# main_2023-11-12.net
KiCad netlist of a schematic drawn in Altium Designer
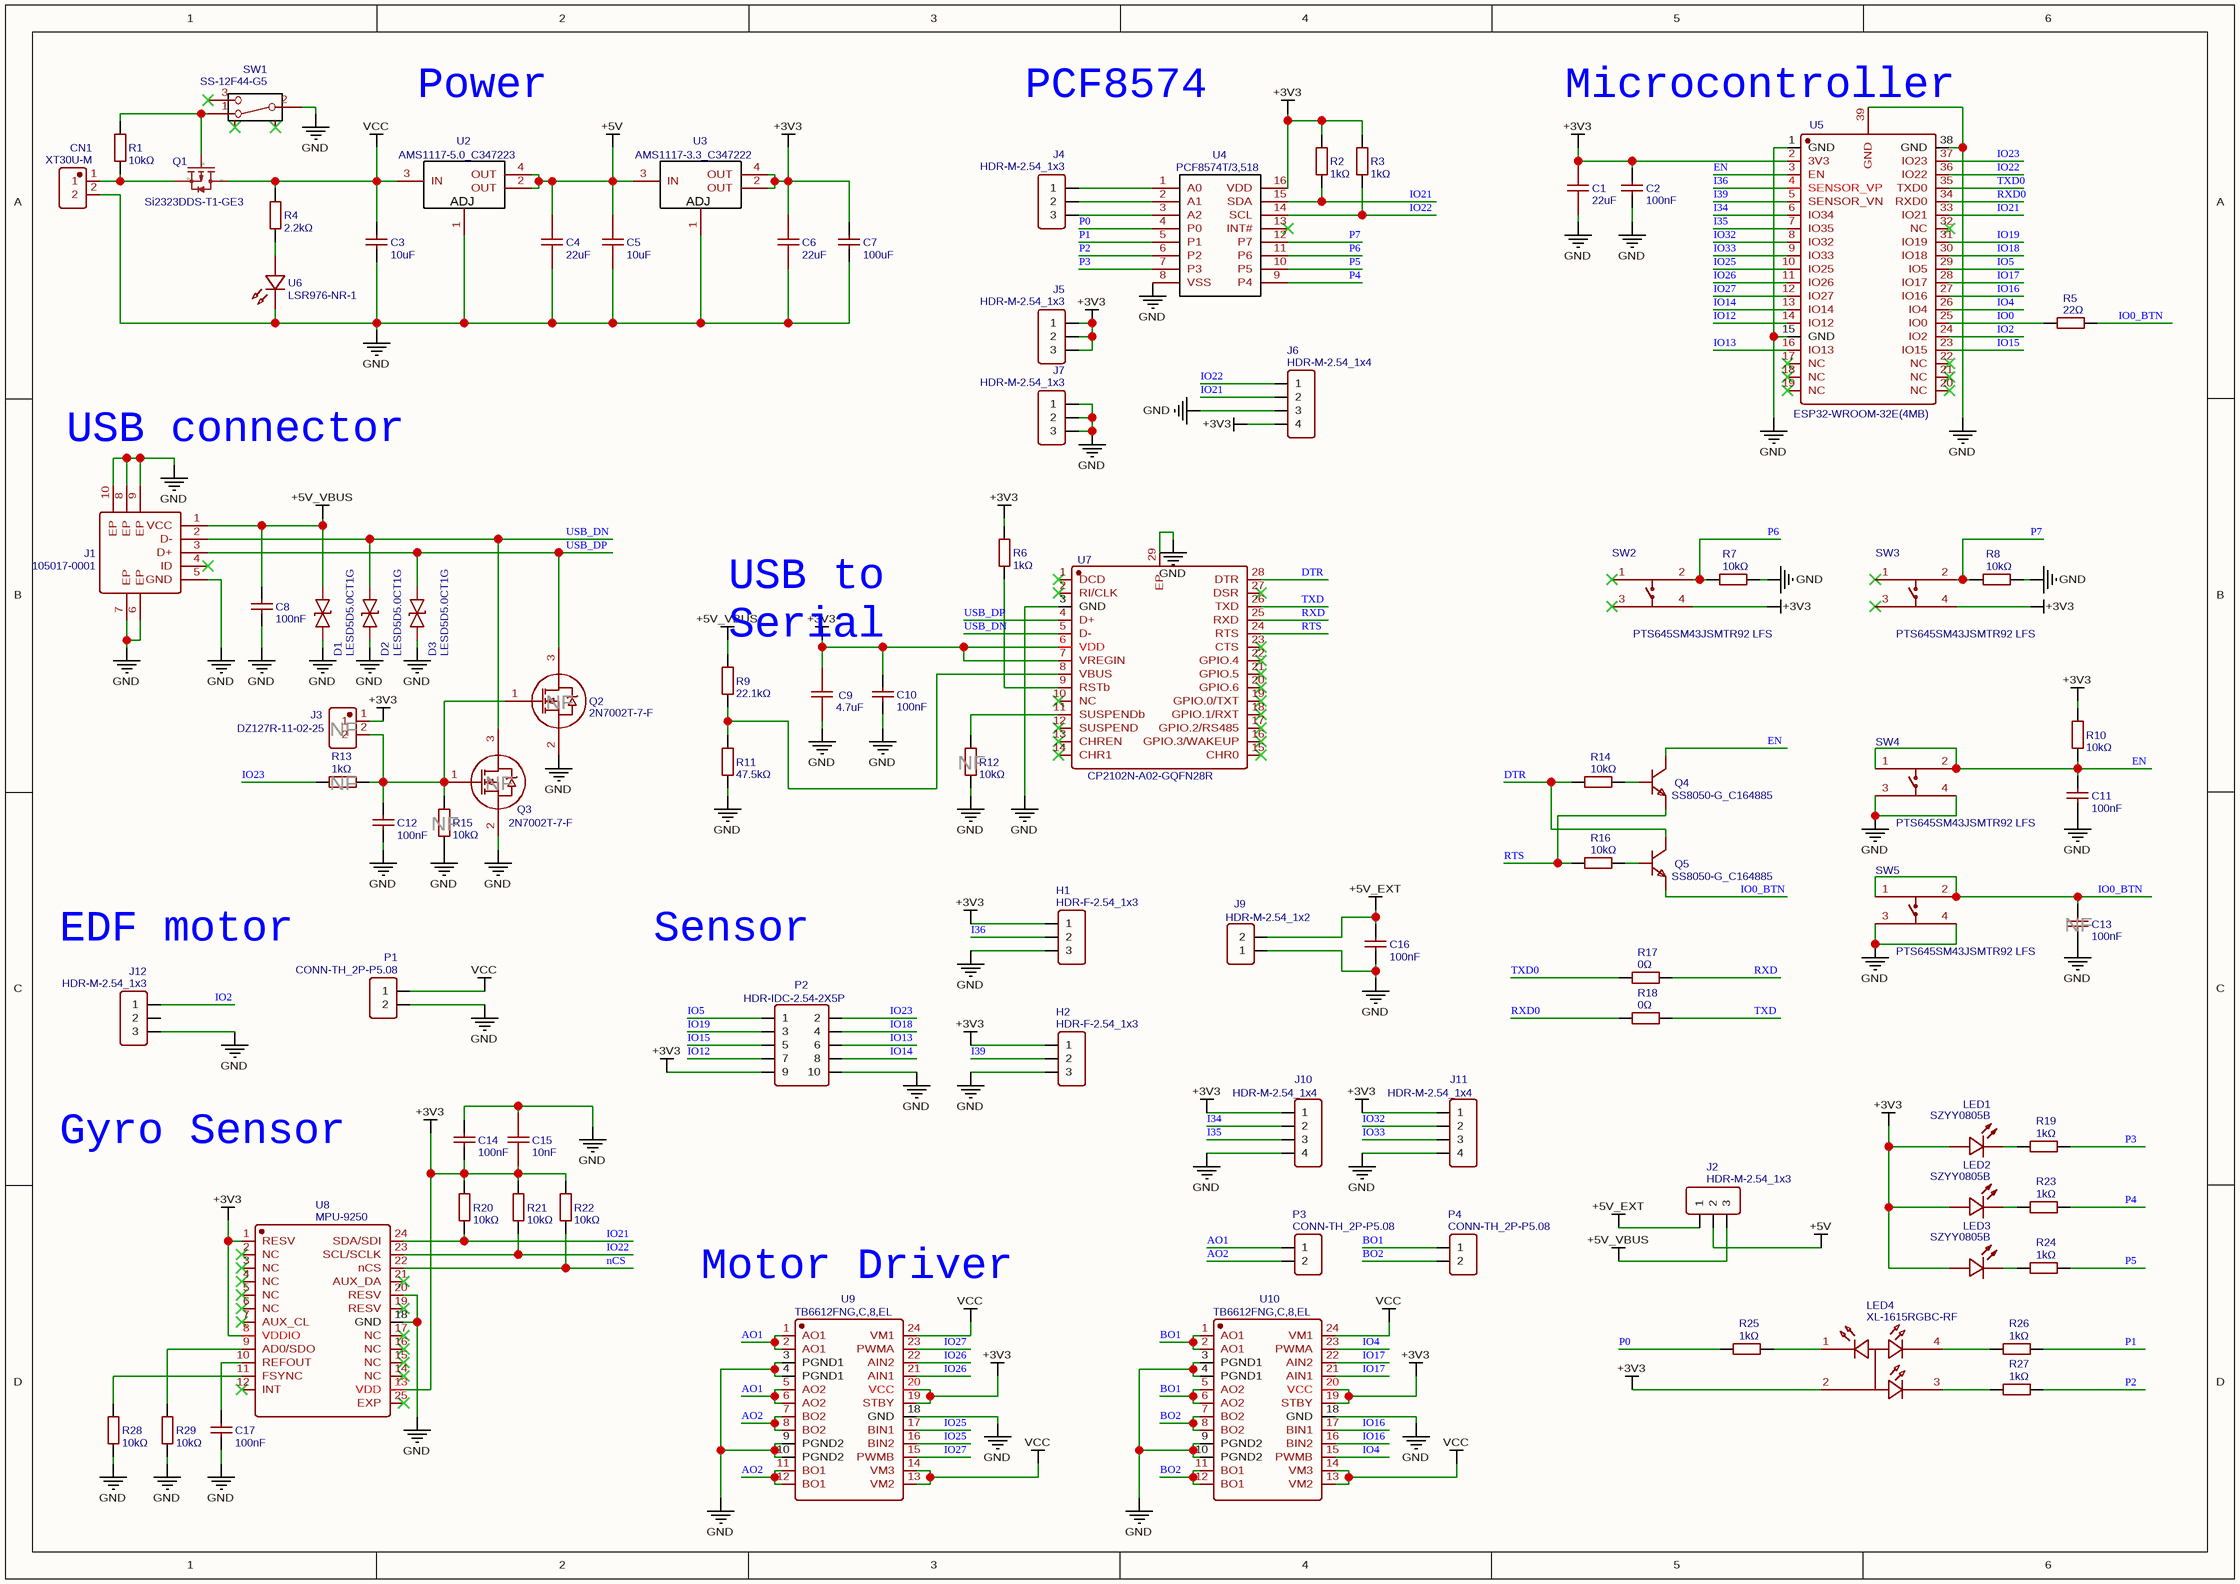
[diagram p0: main_2023-11-12.schdoc]

(export (version "E")
  (design (tool "Eeschema 10.0.6"))
  (components
    (comp (ref "C1")
      (value "22uF")
      (fields
        (field (name "MANUFACTURER") "SAMSUNG(三星)")
        (field (name "MANUFACTURER PART") "CL21A226MAYNNNE")
        (field (name "CONTRIBUTOR") "LCSC")
      )
      (libsource (lib "altium-import") (part "root_3_22uF_"))
    )
    (comp (ref "C2")
      (value "100nF")
      (fields
        (field (name "MANUFACTURER PART") "CL05B104KO5NNNC")
        (field (name "MANUFACTURER") "SAMSUNG(三星)")
      )
      (libsource (lib "altium-import") (part "root_3_100nF_"))
    )
    (comp (ref "C3")
      (value "10uF")
      (fields
        (field (name "MANUFACTURER PART") "CL21A106KOQNNNE")
        (field (name "MANUFACTURER") "SAMSUNG(三星)")
      )
      (libsource (lib "altium-import") (part "root_3_10uF_"))
    )
    (comp (ref "C4")
      (value "22uF")
      (fields
        (field (name "MANUFACTURER") "SAMSUNG(三星)")
        (field (name "MANUFACTURER PART") "CL21A226MAQNNNE")
      )
      (libsource (lib "altium-import") (part "root_3_22uF_"))
    )
    (comp (ref "C5")
      (value "10uF")
      (fields
        (field (name "MANUFACTURER") "SAMSUNG(三星)")
        (field (name "MANUFACTURER PART") "CL05A106MP5NUNC")
        (field (name "CONTRIBUTOR") "LCSC")
      )
      (libsource (lib "") (part "root_3_10uF__1"))
    )
    (comp (ref "C6")
      (value "22uF")
      (fields
        (field (name "MANUFACTURER") "SAMSUNG(三星)")
        (field (name "MANUFACTURER PART") "CL21A226MAQNNNE")
      )
      (libsource (lib "altium-import") (part "root_3_22uF_"))
    )
    (comp (ref "C7")
      (value "100uF")
      (fields
        (field (name "MANUFACTURER PART") "CL31A107MQHNNNE")
        (field (name "MANUFACTURER") "SAMSUNG(三星)")
      )
      (libsource (lib "altium-import") (part "root_3_100uF_"))
    )
    (comp (ref "C8")
      (value "100nF")
      (fields
        (field (name "MANUFACTURER PART") "CL05B104KO5NNNC")
        (field (name "MANUFACTURER") "SAMSUNG(三星)")
      )
      (libsource (lib "altium-import") (part "root_3_100nF_"))
    )
    (comp (ref "C9")
      (value "4.7uF")
      (fields
        (field (name "MANUFACTURER") "SAMSUNG(三星)")
        (field (name "MANUFACTURER PART") "CL05A475KP5NRNC")
        (field (name "CONTRIBUTOR") "LCSC")
      )
      (libsource (lib "altium-import") (part "root_0_4.7uF_"))
    )
    (comp (ref "C10")
      (value "100nF")
      (fields
        (field (name "MANUFACTURER PART") "CL05B104KO5NNNC")
        (field (name "MANUFACTURER") "SAMSUNG(三星)")
      )
      (libsource (lib "altium-import") (part "root_3_100nF_"))
    )
    (comp (ref "C11")
      (value "100nF")
      (fields
        (field (name "MANUFACTURER PART") "CL05B104KO5NNNC")
        (field (name "MANUFACTURER") "SAMSUNG(三星)")
      )
      (libsource (lib "altium-import") (part "root_3_100nF_"))
    )
    (comp (ref "C12")
      (value "100nF")
      (fields
        (field (name "MANUFACTURER PART") "CL05B104KO5NNNC")
        (field (name "MANUFACTURER") "SAMSUNG(三星)")
      )
      (libsource (lib "altium-import") (part "root_3_100nF_"))
    )
    (comp (ref "C13")
      (value "100nF")
      (fields
        (field (name "MANUFACTURER PART") "CL05B104KO5NNNC")
        (field (name "MANUFACTURER") "SAMSUNG(三星)")
      )
      (libsource (lib "altium-import") (part "root_3_100nF_"))
    )
    (comp (ref "C14")
      (value "100nF")
      (fields
        (field (name "MANUFACTURER PART") "CL05B104KO5NNNC")
        (field (name "MANUFACTURER") "SAMSUNG(三星)")
      )
      (libsource (lib "altium-import") (part "root_1_100nF_"))
    )
    (comp (ref "C15")
      (value "10nF")
      (fields
        (field (name "MANUFACTURER") "SAMSUNG(三星)")
        (field (name "MANUFACTURER PART") "CL05B103JO5NNNC")
        (field (name "CONTRIBUTOR") "LCSC")
      )
      (libsource (lib "altium-import") (part "root_0_10nF_"))
    )
    (comp (ref "C16")
      (value "100nF")
      (fields
        (field (name "MANUFACTURER PART") "CL05B104KO5NNNC")
        (field (name "MANUFACTURER") "SAMSUNG(三星)")
      )
      (libsource (lib "altium-import") (part "root_1_100nF_"))
    )
    (comp (ref "C17")
      (value "100nF")
      (fields
        (field (name "MANUFACTURER PART") "CL05B104KO5NNNC")
        (field (name "MANUFACTURER") "SAMSUNG(三星)")
      )
      (libsource (lib "altium-import") (part "root_3_100nF_"))
    )
    (comp (ref "CN1")
      (value "XT30U-M")
      (fields (field (name "MANUFACTURER") "AMASS(艾迈斯)") (field (name "CONTRIBUTOR") "lcsc"))
      (libsource (lib "altium-import") (part "root_0_XT30U-M_"))
    )
    (comp (ref "D1")
      (value "LESD5D5.0CT1G")
      (fields (field (name "MANUFACTURER") "LRC(乐山无线电)") (field (name "CONTRIBUTOR") "LCSC"))
      (libsource (lib "altium-import") (part "root_3_LESD5D5.0CT1G_"))
    )
    (comp (ref "D2")
      (value "LESD5D5.0CT1G")
      (fields (field (name "MANUFACTURER") "LRC(乐山无线电)") (field (name "CONTRIBUTOR") "LCSC"))
      (libsource (lib "altium-import") (part "root_3_LESD5D5.0CT1G_"))
    )
    (comp (ref "D3")
      (value "LESD5D5.0CT1G")
      (fields (field (name "MANUFACTURER") "LRC(乐山无线电)") (field (name "CONTRIBUTOR") "LCSC"))
      (libsource (lib "altium-import") (part "root_3_LESD5D5.0CT1G_"))
    )
    (comp (ref "H1")
      (value "HDR-F-2.54_1x3")
      (fields (field (name "CONTRIBUTOR") "LCEDA_Lib"))
      (libsource (lib "altium-import") (part "root_0_HDR-F-2.54_1x3_"))
    )
    (comp (ref "H2")
      (value "HDR-F-2.54_1x3")
      (fields (field (name "CONTRIBUTOR") "LCEDA_Lib"))
      (libsource (lib "altium-import") (part "root_0_HDR-F-2.54_1x3_"))
    )
    (comp (ref "J1")
      (value "105017-0001")
      (fields
        (field (name "MANUFACTURER") "MOLEX")
        (field (name "MANUFACTURER PART") "1050170001")
        (field (name "CONTRIBUTOR") "LCSC")
      )
      (libsource (lib "altium-import") (part "root_0_105017-0001_"))
    )
    (comp (ref "J2")
      (value "HDR-M-2.54_1x3")
      (fields (field (name "CONTRIBUTOR") "LCEDA_Lib"))
      (libsource (lib "altium-import") (part "root_1_HDR-M-2.54_1x3_"))
    )
    (comp (ref "J3")
      (value "DZ127R-11-02-25")
      (fields (field (name "MANUFACTURER") "DEALON(德艺隆)") (field (name "CONTRIBUTOR") "LCSC"))
      (libsource (lib "altium-import") (part "root_0_DZ127R-11-02-25_"))
    )
    (comp (ref "J4")
      (value "HDR-M-2.54_1x3")
      (fields (field (name "CONTRIBUTOR") "LCEDA_Lib"))
      (libsource (lib "altium-import") (part "root_0_HDR-M-2.54_1x3_"))
    )
    (comp (ref "J5")
      (value "HDR-M-2.54_1x3")
      (fields (field (name "CONTRIBUTOR") "LCEDA_Lib"))
      (libsource (lib "altium-import") (part "root_0_HDR-M-2.54_1x3_"))
    )
    (comp (ref "J6")
      (value "HDR-M-2.54_1x4")
      (fields (field (name "CONTRIBUTOR") "LCEDA_Lib"))
      (libsource (lib "altium-import") (part "root_0_HDR-M-2.54_1x4_"))
    )
    (comp (ref "J7")
      (value "HDR-M-2.54_1x3")
      (fields (field (name "CONTRIBUTOR") "LCEDA_Lib"))
      (libsource (lib "altium-import") (part "root_0_HDR-M-2.54_1x3_"))
    )
    (comp (ref "J9")
      (value "HDR-M-2.54_1x2")
      (fields (field (name "CONTRIBUTOR") "LCEDA_Lib"))
      (libsource (lib "altium-import") (part "root_2_HDR-M-2.54_1x2_"))
    )
    (comp (ref "J10")
      (value "HDR-M-2.54_1x4")
      (fields (field (name "CONTRIBUTOR") "LCEDA_Lib"))
      (libsource (lib "altium-import") (part "root_0_HDR-M-2.54_1x4_"))
    )
    (comp (ref "J11")
      (value "HDR-M-2.54_1x4")
      (fields (field (name "CONTRIBUTOR") "LCEDA_Lib"))
      (libsource (lib "altium-import") (part "root_0_HDR-M-2.54_1x4_"))
    )
    (comp (ref "J12")
      (value "HDR-M-2.54_1x3")
      (fields (field (name "CONTRIBUTOR") "LCEDA_Lib"))
      (libsource (lib "altium-import") (part "root_0_HDR-M-2.54_1x3_"))
    )
    (comp (ref "LED1")
      (value "SZYY0805B")
      (fields (field (name "MANUFACTURER") "yongyu(永裕光电)") (field (name "CONTRIBUTOR") "LCSC"))
      (libsource (lib "altium-import") (part "root_0_SZYY0805B_"))
    )
    (comp (ref "LED2")
      (value "SZYY0805B")
      (fields (field (name "MANUFACTURER") "yongyu(永裕光电)") (field (name "CONTRIBUTOR") "LCSC"))
      (libsource (lib "altium-import") (part "root_0_SZYY0805B_"))
    )
    (comp (ref "LED3")
      (value "SZYY0805B")
      (fields (field (name "MANUFACTURER") "yongyu(永裕光电)") (field (name "CONTRIBUTOR") "LCSC"))
      (libsource (lib "altium-import") (part "root_0_SZYY0805B_"))
    )
    (comp (ref "LED4")
      (value "XL-1615RGBC-RF")
      (fields (field (name "MANUFACTURER") "XINGLIGHT(成兴光)") (field (name "CONTRIBUTOR") "LCSC"))
      (libsource (lib "altium-import") (part "root_0_XL-1615RGBC-RF_"))
    )
    (comp (ref "P1")
      (value "CONN-TH_2P-P5.08")
      (fields (field (name "CONTRIBUTOR") "LCEDA_Lib"))
      (libsource (lib "altium-import") (part "root_0_CONN-TH_2P-P5.08_"))
    )
    (comp (ref "P2")
      (value "HDR-IDC-2.54-2X5P")
      (fields
        (field (name "MANUFACTURER") "BOOMELE")
        (field (name "MANUFACTURER PART") "IDC Box 2.54mm 2X5P")
      )
      (libsource (lib "altium-import") (part "root_0_HDR-IDC-2.54-2X5P_"))
    )
    (comp (ref "P3")
      (value "CONN-TH_2P-P5.08")
      (fields (field (name "CONTRIBUTOR") "LCEDA_Lib"))
      (libsource (lib "") (part "root_0_CONN-TH_2P-P5.08__1"))
    )
    (comp (ref "P4")
      (value "CONN-TH_2P-P5.08")
      (fields (field (name "CONTRIBUTOR") "LCEDA_Lib"))
      (libsource (lib "") (part "root_0_CONN-TH_2P-P5.08__1"))
    )
    (comp (ref "Q1")
      (value "Si2323DDS-T1-GE3")
      (fields (field (name "MANUFACTURER") "VISHAY(威世)") (field (name "CONTRIBUTOR") "LCSC"))
      (libsource (lib "altium-import") (part "root_3_Si2323DDS-T1-GE3_"))
    )
    (comp (ref "Q2")
      (value "2N7002T-7-F")
      (fields (field (name "MANUFACTURER") "DIODES(美台)") (field (name "CONTRIBUTOR") "LCSC"))
      (libsource (lib "altium-import") (part "root_0_2N7002T-7-F_"))
    )
    (comp (ref "Q3")
      (value "2N7002T-7-F")
      (fields (field (name "MANUFACTURER") "DIODES(美台)") (field (name "CONTRIBUTOR") "LCSC"))
      (libsource (lib "altium-import") (part "root_0_2N7002T-7-F_"))
    )
    (comp (ref "Q4")
      (value "SS8050-G_C164885")
      (fields
        (field (name "MANUFACTURER") "CJ(江苏长电/长晶)")
        (field (name "MANUFACTURER PART") "SS8050-G")
        (field (name "CONTRIBUTOR") "LCSC")
      )
      (libsource (lib "altium-import") (part "root_0_SS8050-G_C164885_"))
    )
    (comp (ref "Q5")
      (value "SS8050-G_C164885")
      (fields
        (field (name "MANUFACTURER") "CJ(江苏长电/长晶)")
        (field (name "MANUFACTURER PART") "SS8050-G")
        (field (name "CONTRIBUTOR") "LCSC")
      )
      (libsource (lib "altium-import") (part "root_0_SS8050-G_C164885_"))
    )
    (comp (ref "R1")
      (value "10kΩ")
      (fields
        (field (name "MANUFACTURER") "UNI-ROYAL(厚声)")
        (field (name "MANUFACTURER PART") "0805W8F1002T5E")
      )
      (libsource (lib "altium-import") (part "root_3_10kΩ_"))
    )
    (comp (ref "R2")
      (value "1kΩ")
      (fields
        (field (name "MANUFACTURER") "UNI-ROYAL(厚声)")
        (field (name "MANUFACTURER PART") "0402WGF1001TCE")
      )
      (libsource (lib "altium-import") (part "root_3_1kΩ_"))
    )
    (comp (ref "R3")
      (value "1kΩ")
      (fields
        (field (name "MANUFACTURER") "UNI-ROYAL(厚声)")
        (field (name "MANUFACTURER PART") "0402WGF1001TCE")
      )
      (libsource (lib "altium-import") (part "root_3_1kΩ_"))
    )
    (comp (ref "R4")
      (value "2.2kΩ")
      (fields
        (field (name "MANUFACTURER") "UNI-ROYAL(厚声)")
        (field (name "MANUFACTURER PART") "0603WAF2201T5E")
      )
      (libsource (lib "altium-import") (part "root_3_2.2kΩ_"))
    )
    (comp (ref "R5")
      (value "22Ω")
      (fields
        (field (name "MANUFACTURER") "UNI-ROYAL(厚声)")
        (field (name "MANUFACTURER PART") "0402WGF220JTCE")
      )
      (libsource (lib "altium-import") (part "root_0_22Ω_"))
    )
    (comp (ref "R6")
      (value "1kΩ")
      (fields
        (field (name "MANUFACTURER") "UNI-ROYAL(厚声)")
        (field (name "MANUFACTURER PART") "0402WGF1001TCE")
      )
      (libsource (lib "altium-import") (part "root_3_1kΩ_"))
    )
    (comp (ref "R7")
      (value "10kΩ")
      (fields
        (field (name "MANUFACTURER") "UNI-ROYAL(厚声)")
        (field (name "MANUFACTURER PART") "0402WGF1002TCE")
      )
      (libsource (lib "altium-import") (part "root_0_10kΩ_"))
    )
    (comp (ref "R8")
      (value "10kΩ")
      (fields
        (field (name "MANUFACTURER") "UNI-ROYAL(厚声)")
        (field (name "MANUFACTURER PART") "0402WGF1002TCE")
      )
      (libsource (lib "altium-import") (part "root_0_10kΩ_"))
    )
    (comp (ref "R9")
      (value "22.1kΩ")
      (fields
        (field (name "MANUFACTURER") "UNI-ROYAL(厚声)")
        (field (name "MANUFACTURER PART") "0402WGF2212TCE")
      )
      (libsource (lib "altium-import") (part "root_3_22.1kΩ_"))
    )
    (comp (ref "R10")
      (value "10kΩ")
      (fields
        (field (name "MANUFACTURER") "UNI-ROYAL(厚声)")
        (field (name "MANUFACTURER PART") "0402WGF1002TCE")
      )
      (libsource (lib "altium-import") (part "root_3_10kΩ_"))
    )
    (comp (ref "R11")
      (value "47.5kΩ")
      (fields
        (field (name "MANUFACTURER") "UNI-ROYAL(厚声)")
        (field (name "MANUFACTURER PART") "0402WGF4752TCE")
      )
      (libsource (lib "altium-import") (part "root_3_47.5kΩ_"))
    )
    (comp (ref "R12")
      (value "10kΩ")
      (fields
        (field (name "MANUFACTURER") "UNI-ROYAL(厚声)")
        (field (name "MANUFACTURER PART") "0402WGF1002TCE")
      )
      (libsource (lib "altium-import") (part "root_3_10kΩ_"))
    )
    (comp (ref "R13")
      (value "1kΩ")
      (fields
        (field (name "MANUFACTURER") "UNI-ROYAL(厚声)")
        (field (name "MANUFACTURER PART") "0402WGF1001TCE")
      )
      (libsource (lib "altium-import") (part "root_0_1kΩ_"))
    )
    (comp (ref "R14")
      (value "10kΩ")
      (fields
        (field (name "MANUFACTURER") "UNI-ROYAL(厚声)")
        (field (name "MANUFACTURER PART") "0402WGF1002TCE")
      )
      (libsource (lib "altium-import") (part "root_0_10kΩ_"))
    )
    (comp (ref "R15")
      (value "10kΩ")
      (fields
        (field (name "MANUFACTURER") "UNI-ROYAL(厚声)")
        (field (name "MANUFACTURER PART") "0402WGF1002TCE")
      )
      (libsource (lib "altium-import") (part "root_3_10kΩ_"))
    )
    (comp (ref "R16")
      (value "10kΩ")
      (fields
        (field (name "MANUFACTURER") "UNI-ROYAL(厚声)")
        (field (name "MANUFACTURER PART") "0402WGF1002TCE")
      )
      (libsource (lib "altium-import") (part "root_0_10kΩ_"))
    )
    (comp (ref "R17")
      (value "0Ω")
      (fields
        (field (name "MANUFACTURER") "UNI-ROYAL(厚声)")
        (field (name "MANUFACTURER PART") "0402WGF0000TCE")
      )
      (libsource (lib "altium-import") (part "root_0_0Ω_"))
    )
    (comp (ref "R18")
      (value "0Ω")
      (fields
        (field (name "MANUFACTURER") "UNI-ROYAL(厚声)")
        (field (name "MANUFACTURER PART") "0402WGF0000TCE")
      )
      (libsource (lib "altium-import") (part "root_0_0Ω_"))
    )
    (comp (ref "R19")
      (value "1kΩ")
      (fields
        (field (name "MANUFACTURER") "UNI-ROYAL(厚声)")
        (field (name "MANUFACTURER PART") "0402WGF1001TCE")
      )
      (libsource (lib "altium-import") (part "root_0_1kΩ_"))
    )
    (comp (ref "R20")
      (value "10kΩ")
      (fields
        (field (name "MANUFACTURER") "UNI-ROYAL(厚声)")
        (field (name "MANUFACTURER PART") "0402WGF1002TCE")
      )
      (libsource (lib "altium-import") (part "root_3_10kΩ_"))
    )
    (comp (ref "R21")
      (value "10kΩ")
      (fields
        (field (name "MANUFACTURER") "UNI-ROYAL(厚声)")
        (field (name "MANUFACTURER PART") "0402WGF1002TCE")
      )
      (libsource (lib "altium-import") (part "root_3_10kΩ_"))
    )
    (comp (ref "R22")
      (value "10kΩ")
      (fields
        (field (name "MANUFACTURER") "UNI-ROYAL(厚声)")
        (field (name "MANUFACTURER PART") "0402WGF1002TCE")
      )
      (libsource (lib "altium-import") (part "root_3_10kΩ_"))
    )
    (comp (ref "R23")
      (value "1kΩ")
      (fields
        (field (name "MANUFACTURER") "UNI-ROYAL(厚声)")
        (field (name "MANUFACTURER PART") "0402WGF1001TCE")
      )
      (libsource (lib "altium-import") (part "root_0_1kΩ_"))
    )
    (comp (ref "R24")
      (value "1kΩ")
      (fields
        (field (name "MANUFACTURER") "UNI-ROYAL(厚声)")
        (field (name "MANUFACTURER PART") "0402WGF1001TCE")
      )
      (libsource (lib "altium-import") (part "root_0_1kΩ_"))
    )
    (comp (ref "R25")
      (value "1kΩ")
      (fields
        (field (name "MANUFACTURER") "UNI-ROYAL(厚声)")
        (field (name "MANUFACTURER PART") "0402WGF1001TCE")
      )
      (libsource (lib "altium-import") (part "root_0_1kΩ_"))
    )
    (comp (ref "R26")
      (value "1kΩ")
      (fields
        (field (name "MANUFACTURER") "UNI-ROYAL(厚声)")
        (field (name "MANUFACTURER PART") "0402WGF1001TCE")
      )
      (libsource (lib "altium-import") (part "root_0_1kΩ_"))
    )
    (comp (ref "R27")
      (value "1kΩ")
      (fields
        (field (name "MANUFACTURER") "UNI-ROYAL(厚声)")
        (field (name "MANUFACTURER PART") "0402WGF1001TCE")
      )
      (libsource (lib "altium-import") (part "root_0_1kΩ_"))
    )
    (comp (ref "R28")
      (value "10kΩ")
      (fields
        (field (name "MANUFACTURER") "UNI-ROYAL(厚声)")
        (field (name "MANUFACTURER PART") "0402WGF1002TCE")
      )
      (libsource (lib "altium-import") (part "root_3_10kΩ_"))
    )
    (comp (ref "R29")
      (value "10kΩ")
      (fields
        (field (name "MANUFACTURER") "UNI-ROYAL(厚声)")
        (field (name "MANUFACTURER PART") "0402WGF1002TCE")
      )
      (libsource (lib "altium-import") (part "root_3_10kΩ_"))
    )
    (comp (ref "SW1")
      (value "SS-12F44-G5")
      (fields
        (field (name "MANUFACTURER") "Rectangular Connectors - Contacts")
        (field (name "CONTRIBUTOR") "LCSC")
      )
      (libsource (lib "altium-import") (part "root_0_SS-12F44-G5_"))
    )
    (comp (ref "SW2")
      (value "PTS645SM43JSMTR92 LFS")
      (fields (field (name "MANUFACTURER") "C&K") (field (name "CONTRIBUTOR") "LCSC"))
      (libsource (lib "altium-import") (part "root_0_PTS645SM43JSMTR92 LFS_"))
    )
    (comp (ref "SW3")
      (value "PTS645SM43JSMTR92 LFS")
      (fields (field (name "MANUFACTURER") "C&K") (field (name "CONTRIBUTOR") "LCSC"))
      (libsource (lib "altium-import") (part "root_0_PTS645SM43JSMTR92 LFS_"))
    )
    (comp (ref "SW4")
      (value "PTS645SM43JSMTR92 LFS")
      (fields (field (name "MANUFACTURER") "C&K") (field (name "CONTRIBUTOR") "LCSC"))
      (libsource (lib "altium-import") (part "root_0_PTS645SM43JSMTR92 LFS_"))
    )
    (comp (ref "SW5")
      (value "PTS645SM43JSMTR92 LFS")
      (fields (field (name "MANUFACTURER") "C&K") (field (name "CONTRIBUTOR") "LCSC"))
      (libsource (lib "altium-import") (part "root_0_PTS645SM43JSMTR92 LFS_"))
    )
    (comp (ref "U2")
      (value "AMS1117-5.0_C347223")
      (fields
        (field (name "MANUFACTURER") "UMW(广东友台半导体)")
        (field (name "MANUFACTURER PART") "AMS1117-5.0")
        (field (name "CONTRIBUTOR") "LCEDA_Lib")
      )
      (libsource (lib "altium-import") (part "root_0_AMS1117-5.0_C347223_"))
    )
    (comp (ref "U3")
      (value "AMS1117-3.3_C347222")
      (fields
        (field (name "MANUFACTURER") "UMW(广东友台半导体)")
        (field (name "MANUFACTURER PART") "AMS1117-3.3")
        (field (name "CONTRIBUTOR") "LCEDA_Lib")
      )
      (libsource (lib "altium-import") (part "root_0_AMS1117-3.3_C347222_"))
    )
    (comp (ref "U4")
      (value "PCF8574T/3,518")
      (fields (field (name "MANUFACTURER") "NXP(恩智浦)"))
      (libsource (lib "altium-import") (part "root_0_PCF8574T/3,518_"))
    )
    (comp (ref "U5")
      (value "ESP32-WROOM-32E(4MB)")
      (fields
        (field (name "MANUFACTURER") "ESPRESSIF(乐鑫)")
        (field (name "MANUFACTURER PART") "ESP32-WROOM-32E-N4")
        (field (name "CONTRIBUTOR") "LCSC")
      )
      (libsource (lib "altium-import") (part "root_0_ESP32-WROOM-32E(4MB)_"))
    )
    (comp (ref "U6")
      (value "LSR976-NR-1")
      (fields (field (name "CONTRIBUTOR") "lcsc"))
      (libsource (lib "altium-import") (part "root_1_LSR976-NR-1_"))
    )
    (comp (ref "U7")
      (value "CP2102N-A02-GQFN28R")
      (fields (field (name "MANUFACTURER") "SILICON LABS(芯科)") (field (name "CONTRIBUTOR") "LCSC"))
      (libsource (lib "altium-import") (part "root_0_CP2102N-A02-GQFN28R_"))
    )
    (comp (ref "U8")
      (value "MPU-9250")
      (fields (field (name "MANUFACTURER") "TDK InvenSense(应美盛)") (field (name "CONTRIBUTOR") "LCSC"))
      (libsource (lib "altium-import") (part "root_0_MPU-9250_"))
    )
    (comp (ref "U9")
      (value "TB6612FNG,C,8,EL")
      (fields (field (name "MANUFACTURER") "TOSHIBA(东芝)") (field (name "CONTRIBUTOR") "LCSC"))
      (libsource (lib "altium-import") (part "root_0_TB6612FNG,C,8,EL_"))
    )
    (comp (ref "U10")
      (value "TB6612FNG,C,8,EL")
      (fields (field (name "MANUFACTURER") "TOSHIBA(东芝)") (field (name "CONTRIBUTOR") "LCSC"))
      (libsource (lib "altium-import") (part "root_0_TB6612FNG,C,8,EL_"))
    )
  )
  (nets
    (net (code "1") (name "+3V3") (class "Default")
      (node (ref "C1") (pin "1") (pinfunction "1_1") (pintype "passive"))
      (node (ref "C10") (pin "1") (pinfunction "1_1") (pintype "passive"))
      (node (ref "C14") (pin "1") (pinfunction "1_1") (pintype "passive"))
      (node (ref "C15") (pin "1") (pinfunction "1_1") (pintype "passive"))
      (node (ref "C2") (pin "1") (pinfunction "1_1") (pintype "passive"))
      (node (ref "C6") (pin "1") (pinfunction "1_1") (pintype "passive"))
      (node (ref "C7") (pin "1") (pinfunction "1_1") (pintype "passive"))
      (node (ref "C9") (pin "2") (pinfunction "2_2") (pintype "passive"))
      (node (ref "H1") (pin "1") (pinfunction "1_1") (pintype "passive"))
      (node (ref "H2") (pin "1") (pinfunction "1_1") (pintype "passive"))
      (node (ref "J10") (pin "1") (pinfunction "1_1") (pintype "passive"))
      (node (ref "J11") (pin "1") (pinfunction "1_1") (pintype "passive"))
      (node (ref "J3") (pin "1") (pinfunction "1_1") (pintype "passive"))
      (node (ref "J5") (pin "1") (pinfunction "1_1") (pintype "passive"))
      (node (ref "J5") (pin "2") (pinfunction "2_2") (pintype "passive"))
      (node (ref "J5") (pin "3") (pinfunction "3_3") (pintype "passive"))
      (node (ref "J6") (pin "4") (pinfunction "4_4") (pintype "passive"))
      (node (ref "LED1") (pin "1") (pinfunction "+_1") (pintype "passive"))
      (node (ref "LED2") (pin "1") (pinfunction "+_1") (pintype "passive"))
      (node (ref "LED3") (pin "1") (pinfunction "+_1") (pintype "passive"))
      (node (ref "LED4") (pin "2") (pinfunction "COM+_2") (pintype "passive"))
      (node (ref "P2") (pin "9") (pinfunction "9_9") (pintype "passive"))
      (node (ref "R10") (pin "1") (pinfunction "1_1") (pintype "passive"))
      (node (ref "R2") (pin "1") (pinfunction "1_1") (pintype "passive"))
      (node (ref "R20") (pin "1") (pinfunction "1_1") (pintype "passive"))
      (node (ref "R21") (pin "1") (pinfunction "1_1") (pintype "passive"))
      (node (ref "R22") (pin "1") (pinfunction "1_1") (pintype "passive"))
      (node (ref "R3") (pin "1") (pinfunction "1_1") (pintype "passive"))
      (node (ref "R6") (pin "1") (pinfunction "1_1") (pintype "passive"))
      (node (ref "SW2") (pin "4") (pinfunction "4_4") (pintype "passive"))
      (node (ref "SW3") (pin "4") (pinfunction "4_4") (pintype "passive"))
      (node (ref "U10") (pin "19") (pinfunction "STBY_19") (pintype "passive"))
      (node (ref "U10") (pin "20") (pinfunction "VCC_20") (pintype "passive"))
      (node (ref "U3") (pin "2") (pinfunction "OUT_2") (pintype "passive"))
      (node (ref "U3") (pin "4") (pinfunction "OUT_4") (pintype "passive"))
      (node (ref "U4") (pin "16") (pinfunction "VDD_16") (pintype "passive"))
      (node (ref "U5") (pin "2") (pinfunction "3V3_2") (pintype "passive"))
      (node (ref "U7") (pin "6") (pinfunction "VDD_6") (pintype "passive"))
      (node (ref "U7") (pin "7") (pinfunction "VREGIN_7") (pintype "passive"))
      (node (ref "U8") (pin "1") (pinfunction "RESV_1") (pintype "passive"))
      (node (ref "U8") (pin "13") (pinfunction "VDD_13") (pintype "passive"))
      (node (ref "U8") (pin "8") (pinfunction "VDDIO_8") (pintype "passive"))
      (node (ref "U9") (pin "19") (pinfunction "STBY_19") (pintype "passive"))
      (node (ref "U9") (pin "20") (pinfunction "VCC_20") (pintype "passive"))
    )
    (net (code "2") (name "+5V") (class "Default")
      (node (ref "C4") (pin "1") (pinfunction "1_1") (pintype "passive"))
      (node (ref "C5") (pin "1") (pinfunction "1_1") (pintype "passive"))
      (node (ref "J2") (pin "2") (pinfunction "2_2") (pintype "passive"))
      (node (ref "U2") (pin "2") (pinfunction "OUT_2") (pintype "passive"))
      (node (ref "U2") (pin "4") (pinfunction "OUT_4") (pintype "passive"))
      (node (ref "U3") (pin "3") (pinfunction "IN_3") (pintype "passive"))
    )
    (net (code "3") (name "+5V_EXT") (class "Default")
      (node (ref "C16") (pin "2") (pinfunction "2_2") (pintype "passive"))
      (node (ref "J2") (pin "1") (pinfunction "1_1") (pintype "passive"))
      (node (ref "J9") (pin "2") (pinfunction "2_2") (pintype "passive"))
    )
    (net (code "4") (name "+5V_VBUS") (class "Default")
      (node (ref "C8") (pin "1") (pinfunction "1_1") (pintype "passive"))
      (node (ref "D1") (pin "1") (pinfunction "1_1") (pintype "passive"))
      (node (ref "J1") (pin "1") (pinfunction "VCC_1") (pintype "passive"))
      (node (ref "J2") (pin "3") (pinfunction "3_3") (pintype "passive"))
      (node (ref "R9") (pin "1") (pinfunction "1_1") (pintype "passive"))
    )
    (net (code "5") (name "/AO1") (class "Default")
      (node (ref "P3") (pin "1") (pinfunction "1_1") (pintype "passive"))
      (node (ref "U9") (pin "1") (pinfunction "AO1_1") (pintype "passive"))
      (node (ref "U9") (pin "2") (pinfunction "AO1_2") (pintype "passive"))
      (node (ref "U9") (pin "5") (pinfunction "AO2_5") (pintype "passive"))
      (node (ref "U9") (pin "6") (pinfunction "AO2_6") (pintype "passive"))
    )
    (net (code "6") (name "/AO2") (class "Default")
      (node (ref "P3") (pin "2") (pinfunction "2_2") (pintype "passive"))
      (node (ref "U9") (pin "11") (pinfunction "BO1_11") (pintype "passive"))
      (node (ref "U9") (pin "12") (pinfunction "BO1_12") (pintype "passive"))
      (node (ref "U9") (pin "7") (pinfunction "BO2_7") (pintype "passive"))
      (node (ref "U9") (pin "8") (pinfunction "BO2_8") (pintype "passive"))
    )
    (net (code "7") (name "/BO1") (class "Default")
      (node (ref "P4") (pin "1") (pinfunction "1_1") (pintype "passive"))
      (node (ref "U10") (pin "1") (pinfunction "AO1_1") (pintype "passive"))
      (node (ref "U10") (pin "2") (pinfunction "AO1_2") (pintype "passive"))
      (node (ref "U10") (pin "5") (pinfunction "AO2_5") (pintype "passive"))
      (node (ref "U10") (pin "6") (pinfunction "AO2_6") (pintype "passive"))
    )
    (net (code "8") (name "/BO2") (class "Default")
      (node (ref "P4") (pin "2") (pinfunction "2_2") (pintype "passive"))
      (node (ref "U10") (pin "11") (pinfunction "BO1_11") (pintype "passive"))
      (node (ref "U10") (pin "12") (pinfunction "BO1_12") (pintype "passive"))
      (node (ref "U10") (pin "7") (pinfunction "BO2_7") (pintype "passive"))
      (node (ref "U10") (pin "8") (pinfunction "BO2_8") (pintype "passive"))
    )
    (net (code "9") (name "/DTR") (class "Default")
      (node (ref "Q5") (pin "3") (pinfunction "C_3") (pintype "passive"))
      (node (ref "R14") (pin "1") (pinfunction "1_1") (pintype "passive"))
      (node (ref "U7") (pin "28") (pinfunction "DTR_28") (pintype "passive"))
    )
    (net (code "10") (name "/EN") (class "Default")
      (node (ref "C11") (pin "1") (pinfunction "1_1") (pintype "passive"))
      (node (ref "Q4") (pin "3") (pinfunction "C_3") (pintype "passive"))
      (node (ref "R10") (pin "2") (pinfunction "2_2") (pintype "passive"))
      (node (ref "SW4") (pin "1") (pinfunction "1_1") (pintype "passive"))
      (node (ref "SW4") (pin "2") (pinfunction "2_2") (pintype "passive"))
      (node (ref "U5") (pin "3") (pinfunction "EN_3") (pintype "passive"))
    )
    (net (code "11") (name "/I34") (class "Default")
      (node (ref "J10") (pin "2") (pinfunction "2_2") (pintype "passive"))
      (node (ref "U5") (pin "6") (pinfunction "IO34_6") (pintype "passive"))
    )
    (net (code "12") (name "/I35") (class "Default")
      (node (ref "J10") (pin "3") (pinfunction "3_3") (pintype "passive"))
      (node (ref "U5") (pin "7") (pinfunction "IO35_7") (pintype "passive"))
    )
    (net (code "13") (name "/I36") (class "Default")
      (node (ref "H1") (pin "2") (pinfunction "2_2") (pintype "passive"))
      (node (ref "U5") (pin "4") (pinfunction "SENSOR_VP_4") (pintype "passive"))
    )
    (net (code "14") (name "/I39") (class "Default")
      (node (ref "H2") (pin "2") (pinfunction "2_2") (pintype "passive"))
      (node (ref "U5") (pin "5") (pinfunction "SENSOR_VN_5") (pintype "passive"))
    )
    (net (code "15") (name "/IO0") (class "Default")
      (node (ref "R5") (pin "1") (pinfunction "1_1") (pintype "passive"))
      (node (ref "U5") (pin "25") (pinfunction "IO0_25") (pintype "passive"))
    )
    (net (code "16") (name "/IO0_BTN") (class "Default")
      (node (ref "C13") (pin "1") (pinfunction "1_1") (pintype "passive"))
      (node (ref "Q5") (pin "2") (pinfunction "E_2") (pintype "passive"))
      (node (ref "R5") (pin "2") (pinfunction "2_2") (pintype "passive"))
      (node (ref "SW5") (pin "1") (pinfunction "1_1") (pintype "passive"))
      (node (ref "SW5") (pin "2") (pinfunction "2_2") (pintype "passive"))
    )
    (net (code "17") (name "/IO2") (class "Default")
      (node (ref "J12") (pin "1") (pinfunction "1_1") (pintype "passive"))
      (node (ref "U5") (pin "24") (pinfunction "IO2_24") (pintype "passive"))
    )
    (net (code "18") (name "/IO4") (class "Default")
      (node (ref "U10") (pin "15") (pinfunction "PWMB_15") (pintype "passive"))
      (node (ref "U10") (pin "23") (pinfunction "PWMA_23") (pintype "passive"))
      (node (ref "U5") (pin "26") (pinfunction "IO4_26") (pintype "passive"))
    )
    (net (code "19") (name "/IO5") (class "Default")
      (node (ref "P2") (pin "1") (pinfunction "1_1") (pintype "passive"))
      (node (ref "U5") (pin "29") (pinfunction "IO5_29") (pintype "passive"))
    )
    (net (code "20") (name "/IO12") (class "Default")
      (node (ref "P2") (pin "7") (pinfunction "7_7") (pintype "passive"))
      (node (ref "U5") (pin "14") (pinfunction "IO12_14") (pintype "passive"))
    )
    (net (code "21") (name "/IO13") (class "Default")
      (node (ref "P2") (pin "6") (pinfunction "6_6") (pintype "passive"))
      (node (ref "U5") (pin "16") (pinfunction "IO13_16") (pintype "passive"))
    )
    (net (code "22") (name "/IO14") (class "Default")
      (node (ref "P2") (pin "8") (pinfunction "8_8") (pintype "passive"))
      (node (ref "U5") (pin "13") (pinfunction "IO14_13") (pintype "passive"))
    )
    (net (code "23") (name "/IO15") (class "Default")
      (node (ref "P2") (pin "5") (pinfunction "5_5") (pintype "passive"))
      (node (ref "U5") (pin "23") (pinfunction "IO15_23") (pintype "passive"))
    )
    (net (code "24") (name "/IO16") (class "Default")
      (node (ref "U10") (pin "16") (pinfunction "BIN2_16") (pintype "passive"))
      (node (ref "U10") (pin "17") (pinfunction "BIN1_17") (pintype "passive"))
      (node (ref "U5") (pin "27") (pinfunction "IO16_27") (pintype "passive"))
    )
    (net (code "25") (name "/IO17") (class "Default")
      (node (ref "U10") (pin "21") (pinfunction "AIN1_21") (pintype "passive"))
      (node (ref "U10") (pin "22") (pinfunction "AIN2_22") (pintype "passive"))
      (node (ref "U5") (pin "28") (pinfunction "IO17_28") (pintype "passive"))
    )
    (net (code "26") (name "/IO18") (class "Default")
      (node (ref "P2") (pin "4") (pinfunction "4_4") (pintype "passive"))
      (node (ref "U5") (pin "30") (pinfunction "IO18_30") (pintype "passive"))
    )
    (net (code "27") (name "/IO19") (class "Default")
      (node (ref "P2") (pin "3") (pinfunction "3_3") (pintype "passive"))
      (node (ref "U5") (pin "31") (pinfunction "IO19_31") (pintype "passive"))
    )
    (net (code "28") (name "/IO21") (class "Default")
      (node (ref "J6") (pin "2") (pinfunction "2_2") (pintype "passive"))
      (node (ref "R2") (pin "2") (pinfunction "2_2") (pintype "passive"))
      (node (ref "R20") (pin "2") (pinfunction "2_2") (pintype "passive"))
      (node (ref "U4") (pin "15") (pinfunction "SDA_15") (pintype "passive"))
      (node (ref "U5") (pin "33") (pinfunction "IO21_33") (pintype "passive"))
      (node (ref "U8") (pin "24") (pinfunction "SDA/SDI_24") (pintype "passive"))
    )
    (net (code "29") (name "/IO22") (class "Default")
      (node (ref "J6") (pin "1") (pinfunction "1_1") (pintype "passive"))
      (node (ref "R21") (pin "2") (pinfunction "2_2") (pintype "passive"))
      (node (ref "R3") (pin "2") (pinfunction "2_2") (pintype "passive"))
      (node (ref "U4") (pin "14") (pinfunction "SCL_14") (pintype "passive"))
      (node (ref "U5") (pin "36") (pinfunction "IO22_36") (pintype "passive"))
      (node (ref "U8") (pin "23") (pinfunction "SCL/SCLK_23") (pintype "passive"))
    )
    (net (code "30") (name "/IO23") (class "Default")
      (node (ref "P2") (pin "2") (pinfunction "2_2") (pintype "passive"))
      (node (ref "R13") (pin "1") (pinfunction "1_1") (pintype "passive"))
      (node (ref "U5") (pin "37") (pinfunction "IO23_37") (pintype "passive"))
    )
    (net (code "31") (name "/IO25") (class "Default")
      (node (ref "U5") (pin "10") (pinfunction "IO25_10") (pintype "passive"))
      (node (ref "U9") (pin "16") (pinfunction "BIN2_16") (pintype "passive"))
      (node (ref "U9") (pin "17") (pinfunction "BIN1_17") (pintype "passive"))
    )
    (net (code "32") (name "/IO26") (class "Default")
      (node (ref "U5") (pin "11") (pinfunction "IO26_11") (pintype "passive"))
      (node (ref "U9") (pin "21") (pinfunction "AIN1_21") (pintype "passive"))
      (node (ref "U9") (pin "22") (pinfunction "AIN2_22") (pintype "passive"))
    )
    (net (code "33") (name "/IO27") (class "Default")
      (node (ref "U5") (pin "12") (pinfunction "IO27_12") (pintype "passive"))
      (node (ref "U9") (pin "15") (pinfunction "PWMB_15") (pintype "passive"))
      (node (ref "U9") (pin "23") (pinfunction "PWMA_23") (pintype "passive"))
    )
    (net (code "34") (name "/IO32") (class "Default")
      (node (ref "J11") (pin "2") (pinfunction "2_2") (pintype "passive"))
      (node (ref "U5") (pin "8") (pinfunction "IO32_8") (pintype "passive"))
    )
    (net (code "35") (name "/IO33") (class "Default")
      (node (ref "J11") (pin "3") (pinfunction "3_3") (pintype "passive"))
      (node (ref "U5") (pin "9") (pinfunction "IO33_9") (pintype "passive"))
    )
    (net (code "36") (name "/P0") (class "Default")
      (node (ref "R25") (pin "1") (pinfunction "1_1") (pintype "passive"))
      (node (ref "U4") (pin "4") (pinfunction "P0_4") (pintype "passive"))
    )
    (net (code "37") (name "/P1") (class "Default")
      (node (ref "R26") (pin "2") (pinfunction "2_2") (pintype "passive"))
      (node (ref "U4") (pin "5") (pinfunction "P1_5") (pintype "passive"))
    )
    (net (code "38") (name "/P2") (class "Default")
      (node (ref "R27") (pin "2") (pinfunction "2_2") (pintype "passive"))
      (node (ref "U4") (pin "6") (pinfunction "P2_6") (pintype "passive"))
    )
    (net (code "39") (name "/P3") (class "Default")
      (node (ref "R19") (pin "2") (pinfunction "2_2") (pintype "passive"))
      (node (ref "U4") (pin "7") (pinfunction "P3_7") (pintype "passive"))
    )
    (net (code "40") (name "/P4") (class "Default")
      (node (ref "R23") (pin "2") (pinfunction "2_2") (pintype "passive"))
      (node (ref "U4") (pin "9") (pinfunction "P4_9") (pintype "passive"))
    )
    (net (code "41") (name "/P5") (class "Default")
      (node (ref "R24") (pin "2") (pinfunction "2_2") (pintype "passive"))
      (node (ref "U4") (pin "10") (pinfunction "P5_10") (pintype "passive"))
    )
    (net (code "42") (name "/P6") (class "Default")
      (node (ref "R7") (pin "1") (pinfunction "1_1") (pintype "passive"))
      (node (ref "SW2") (pin "2") (pinfunction "2_2") (pintype "passive"))
      (node (ref "U4") (pin "11") (pinfunction "P6_11") (pintype "passive"))
    )
    (net (code "43") (name "/P7") (class "Default")
      (node (ref "R8") (pin "1") (pinfunction "1_1") (pintype "passive"))
      (node (ref "SW3") (pin "2") (pinfunction "2_2") (pintype "passive"))
      (node (ref "U4") (pin "12") (pinfunction "P7_12") (pintype "passive"))
    )
    (net (code "44") (name "/RTS") (class "Default")
      (node (ref "Q4") (pin "2") (pinfunction "E_2") (pintype "passive"))
      (node (ref "R16") (pin "1") (pinfunction "1_1") (pintype "passive"))
      (node (ref "U7") (pin "24") (pinfunction "RTS_24") (pintype "passive"))
    )
    (net (code "45") (name "/RXD") (class "Default")
      (node (ref "R17") (pin "2") (pinfunction "2_2") (pintype "passive"))
      (node (ref "U7") (pin "25") (pinfunction "RXD_25") (pintype "passive"))
    )
    (net (code "46") (name "/RXD0") (class "Default")
      (node (ref "R18") (pin "1") (pinfunction "1_1") (pintype "passive"))
      (node (ref "U5") (pin "34") (pinfunction "RXD0_34") (pintype "passive"))
    )
    (net (code "47") (name "/TXD") (class "Default")
      (node (ref "R18") (pin "2") (pinfunction "2_2") (pintype "passive"))
      (node (ref "U7") (pin "26") (pinfunction "TXD_26") (pintype "passive"))
    )
    (net (code "48") (name "/TXD0") (class "Default")
      (node (ref "R17") (pin "1") (pinfunction "1_1") (pintype "passive"))
      (node (ref "U5") (pin "35") (pinfunction "TXD0_35") (pintype "passive"))
    )
    (net (code "49") (name "/USB_DN") (class "Default")
      (node (ref "D2") (pin "1") (pinfunction "1_1") (pintype "passive"))
      (node (ref "J1") (pin "2") (pinfunction "D-_2") (pintype "passive"))
      (node (ref "Q3") (pin "3") (pinfunction "D_3") (pintype "passive"))
      (node (ref "U7") (pin "5") (pinfunction "D-_5") (pintype "passive"))
    )
    (net (code "50") (name "/USB_DP") (class "Default")
      (node (ref "D3") (pin "1") (pinfunction "1_1") (pintype "passive"))
      (node (ref "J1") (pin "3") (pinfunction "D+_3") (pintype "passive"))
      (node (ref "Q2") (pin "3") (pinfunction "D_3") (pintype "passive"))
      (node (ref "U7") (pin "4") (pinfunction "D+_4") (pintype "passive"))
    )
    (net (code "51") (name "/nCS") (class "Default")
      (node (ref "R22") (pin "2") (pinfunction "2_2") (pintype "passive"))
      (node (ref "U8") (pin "22") (pinfunction "nCS_22") (pintype "passive"))
    )
    (net (code "52") (name "GND") (class "Default")
      (node (ref "C1") (pin "2") (pinfunction "2_2") (pintype "passive"))
      (node (ref "C10") (pin "2") (pinfunction "2_2") (pintype "passive"))
      (node (ref "C11") (pin "2") (pinfunction "2_2") (pintype "passive"))
      (node (ref "C12") (pin "2") (pinfunction "2_2") (pintype "passive"))
      (node (ref "C13") (pin "2") (pinfunction "2_2") (pintype "passive"))
      (node (ref "C14") (pin "2") (pinfunction "2_2") (pintype "passive"))
      (node (ref "C15") (pin "2") (pinfunction "2_2") (pintype "passive"))
      (node (ref "C16") (pin "1") (pinfunction "1_1") (pintype "passive"))
      (node (ref "C17") (pin "2") (pinfunction "2_2") (pintype "passive"))
      (node (ref "C2") (pin "2") (pinfunction "2_2") (pintype "passive"))
      (node (ref "C3") (pin "2") (pinfunction "2_2") (pintype "passive"))
      (node (ref "C4") (pin "2") (pinfunction "2_2") (pintype "passive"))
      (node (ref "C5") (pin "2") (pinfunction "2_2") (pintype "passive"))
      (node (ref "C6") (pin "2") (pinfunction "2_2") (pintype "passive"))
      (node (ref "C7") (pin "2") (pinfunction "2_2") (pintype "passive"))
      (node (ref "C8") (pin "2") (pinfunction "2_2") (pintype "passive"))
      (node (ref "C9") (pin "1") (pinfunction "1_1") (pintype "passive"))
      (node (ref "CN1") (pin "2") (pinfunction "2_2") (pintype "passive"))
      (node (ref "D1") (pin "2") (pinfunction "2_2") (pintype "passive"))
      (node (ref "D2") (pin "2") (pinfunction "2_2") (pintype "passive"))
      (node (ref "D3") (pin "2") (pinfunction "2_2") (pintype "passive"))
      (node (ref "H1") (pin "3") (pinfunction "3_3") (pintype "passive"))
      (node (ref "H2") (pin "3") (pinfunction "3_3") (pintype "passive"))
      (node (ref "J1") (pin "10") (pinfunction "EP_10") (pintype "passive"))
      (node (ref "J1") (pin "5") (pinfunction "GND_5") (pintype "passive"))
      (node (ref "J1") (pin "6") (pinfunction "EP_6") (pintype "passive"))
      (node (ref "J1") (pin "7") (pinfunction "EP_7") (pintype "passive"))
      (node (ref "J1") (pin "8") (pinfunction "EP_8") (pintype "passive"))
      (node (ref "J1") (pin "9") (pinfunction "EP_9") (pintype "passive"))
      (node (ref "J10") (pin "4") (pinfunction "4_4") (pintype "passive"))
      (node (ref "J11") (pin "4") (pinfunction "4_4") (pintype "passive"))
      (node (ref "J12") (pin "3") (pinfunction "3_3") (pintype "passive"))
      (node (ref "J6") (pin "3") (pinfunction "3_3") (pintype "passive"))
      (node (ref "J7") (pin "1") (pinfunction "1_1") (pintype "passive"))
      (node (ref "J7") (pin "2") (pinfunction "2_2") (pintype "passive"))
      (node (ref "J7") (pin "3") (pinfunction "3_3") (pintype "passive"))
      (node (ref "J9") (pin "1") (pinfunction "1_1") (pintype "passive"))
      (node (ref "P1") (pin "2") (pinfunction "2_2") (pintype "passive"))
      (node (ref "P2") (pin "10") (pinfunction "10_10") (pintype "passive"))
      (node (ref "Q2") (pin "2") (pinfunction "S_2") (pintype "passive"))
      (node (ref "Q3") (pin "2") (pinfunction "S_2") (pintype "passive"))
      (node (ref "R11") (pin "2") (pinfunction "2_2") (pintype "passive"))
      (node (ref "R12") (pin "2") (pinfunction "2_2") (pintype "passive"))
      (node (ref "R15") (pin "2") (pinfunction "2_2") (pintype "passive"))
      (node (ref "R28") (pin "2") (pinfunction "2_2") (pintype "passive"))
      (node (ref "R29") (pin "2") (pinfunction "2_2") (pintype "passive"))
      (node (ref "R7") (pin "2") (pinfunction "2_2") (pintype "passive"))
      (node (ref "R8") (pin "2") (pinfunction "2_2") (pintype "passive"))
      (node (ref "SW1") (pin "2") (pinfunction "2_2") (pintype "passive"))
      (node (ref "SW4") (pin "3") (pinfunction "3_3") (pintype "passive"))
      (node (ref "SW4") (pin "4") (pinfunction "4_4") (pintype "passive"))
      (node (ref "SW5") (pin "3") (pinfunction "3_3") (pintype "passive"))
      (node (ref "SW5") (pin "4") (pinfunction "4_4") (pintype "passive"))
      (node (ref "U10") (pin "10") (pinfunction "PGND2_10") (pintype "passive"))
      (node (ref "U10") (pin "18") (pinfunction "GND_18") (pintype "passive"))
      (node (ref "U10") (pin "3") (pinfunction "PGND1_3") (pintype "passive"))
      (node (ref "U10") (pin "4") (pinfunction "PGND1_4") (pintype "passive"))
      (node (ref "U10") (pin "9") (pinfunction "PGND2_9") (pintype "passive"))
      (node (ref "U2") (pin "1") (pinfunction "ADJ_1") (pintype "passive"))
      (node (ref "U3") (pin "1") (pinfunction "ADJ_1") (pintype "passive"))
      (node (ref "U4") (pin "8") (pinfunction "VSS_8") (pintype "passive"))
      (node (ref "U5") (pin "1") (pinfunction "GND_1") (pintype "passive"))
      (node (ref "U5") (pin "15") (pinfunction "GND_15") (pintype "passive"))
      (node (ref "U5") (pin "38") (pinfunction "GND_38") (pintype "passive"))
      (node (ref "U5") (pin "39") (pinfunction "GND_39") (pintype "passive"))
      (node (ref "U6") (pin "1") (pinfunction "K_1") (pintype "passive"))
      (node (ref "U7") (pin "29") (pinfunction "EP_29") (pintype "passive"))
      (node (ref "U7") (pin "3") (pinfunction "GND_3") (pintype "passive"))
      (node (ref "U8") (pin "18") (pinfunction "GND_18") (pintype "passive"))
      (node (ref "U8") (pin "20") (pinfunction "RESV_20") (pintype "passive"))
      (node (ref "U9") (pin "10") (pinfunction "PGND2_10") (pintype "passive"))
      (node (ref "U9") (pin "18") (pinfunction "GND_18") (pintype "passive"))
      (node (ref "U9") (pin "3") (pinfunction "PGND1_3") (pintype "passive"))
      (node (ref "U9") (pin "4") (pinfunction "PGND1_4") (pintype "passive"))
      (node (ref "U9") (pin "9") (pinfunction "PGND2_9") (pintype "passive"))
    )
    (net (code "53") (name "Net-(LED1--)") (class "Default")
      (node (ref "LED1") (pin "2") (pinfunction "-_2") (pintype "passive"))
      (node (ref "R19") (pin "1") (pinfunction "1_1") (pintype "passive"))
    )
    (net (code "54") (name "Net-(LED2--)") (class "Default")
      (node (ref "LED2") (pin "2") (pinfunction "-_2") (pintype "passive"))
      (node (ref "R23") (pin "1") (pinfunction "1_1") (pintype "passive"))
    )
    (net (code "55") (name "Net-(LED3--)") (class "Default")
      (node (ref "LED3") (pin "2") (pinfunction "-_2") (pintype "passive"))
      (node (ref "R24") (pin "1") (pinfunction "1_1") (pintype "passive"))
    )
    (net (code "56") (name "Net-(LED4-B-)") (class "Default")
      (node (ref "LED4") (pin "3") (pinfunction "B-_3") (pintype "passive"))
      (node (ref "R27") (pin "1") (pinfunction "1_1") (pintype "passive"))
    )
    (net (code "57") (name "Net-(LED4-G-)") (class "Default")
      (node (ref "LED4") (pin "4") (pinfunction "G-_4") (pintype "passive"))
      (node (ref "R26") (pin "1") (pinfunction "1_1") (pintype "passive"))
    )
    (net (code "58") (name "Net-(LED4-R-)") (class "Default")
      (node (ref "LED4") (pin "1") (pinfunction "R-_1") (pintype "passive"))
      (node (ref "R25") (pin "2") (pinfunction "2_2") (pintype "passive"))
    )
    (net (code "59") (name "Net-(Q1-G)") (class "Default")
      (node (ref "Q1") (pin "1") (pinfunction "G_1") (pintype "passive"))
      (node (ref "R1") (pin "1") (pinfunction "1_1") (pintype "passive"))
      (node (ref "SW1") (pin "1") (pinfunction "1_1") (pintype "passive"))
    )
    (net (code "60") (name "Net-(Q1-S)") (class "Default")
      (node (ref "CN1") (pin "1") (pinfunction "1_1") (pintype "passive"))
      (node (ref "Q1") (pin "2") (pinfunction "S_2") (pintype "passive"))
      (node (ref "R1") (pin "2") (pinfunction "2_2") (pintype "passive"))
    )
    (net (code "61") (name "Net-(Q2-G)") (class "Default")
      (node (ref "C12") (pin "1") (pinfunction "1_1") (pintype "passive"))
      (node (ref "J3") (pin "2") (pinfunction "2_2") (pintype "passive"))
      (node (ref "Q2") (pin "1") (pinfunction "G_1") (pintype "passive"))
      (node (ref "Q3") (pin "1") (pinfunction "G_1") (pintype "passive"))
      (node (ref "R13") (pin "2") (pinfunction "2_2") (pintype "passive"))
      (node (ref "R15") (pin "1") (pinfunction "1_1") (pintype "passive"))
    )
    (net (code "62") (name "Net-(Q4-B)") (class "Default")
      (node (ref "Q4") (pin "1") (pinfunction "B_1") (pintype "passive"))
      (node (ref "R14") (pin "2") (pinfunction "2_2") (pintype "passive"))
    )
    (net (code "63") (name "Net-(Q5-B)") (class "Default")
      (node (ref "Q5") (pin "1") (pinfunction "B_1") (pintype "passive"))
      (node (ref "R16") (pin "2") (pinfunction "2_2") (pintype "passive"))
    )
    (net (code "64") (name "Net-(U4-A0)") (class "Default")
      (node (ref "J4") (pin "1") (pinfunction "1_1") (pintype "passive"))
      (node (ref "U4") (pin "1") (pinfunction "A0_1") (pintype "passive"))
    )
    (net (code "65") (name "Net-(U4-A1)") (class "Default")
      (node (ref "J4") (pin "2") (pinfunction "2_2") (pintype "passive"))
      (node (ref "U4") (pin "2") (pinfunction "A1_2") (pintype "passive"))
    )
    (net (code "66") (name "Net-(U4-A2)") (class "Default")
      (node (ref "J4") (pin "3") (pinfunction "3_3") (pintype "passive"))
      (node (ref "U4") (pin "3") (pinfunction "A2_3") (pintype "passive"))
    )
    (net (code "67") (name "Net-(U6-A)") (class "Default")
      (node (ref "R4") (pin "2") (pinfunction "2_2") (pintype "passive"))
      (node (ref "U6") (pin "2") (pinfunction "A_2") (pintype "passive"))
    )
    (net (code "68") (name "Net-(U7-RSTb)") (class "Default")
      (node (ref "R6") (pin "2") (pinfunction "2_2") (pintype "passive"))
      (node (ref "U7") (pin "9") (pinfunction "RSTb_9") (pintype "passive"))
    )
    (net (code "69") (name "Net-(U7-SUSPENDb)") (class "Default")
      (node (ref "R12") (pin "1") (pinfunction "1_1") (pintype "passive"))
      (node (ref "U7") (pin "11") (pinfunction "SUSPENDb_11") (pintype "passive"))
    )
    (net (code "70") (name "Net-(U7-VBUS)") (class "Default")
      (node (ref "R11") (pin "1") (pinfunction "1_1") (pintype "passive"))
      (node (ref "R9") (pin "2") (pinfunction "2_2") (pintype "passive"))
      (node (ref "U7") (pin "8") (pinfunction "VBUS_8") (pintype "passive"))
    )
    (net (code "71") (name "Net-(U8-AD0{slash}SDO)") (class "Default")
      (node (ref "R29") (pin "1") (pinfunction "1_1") (pintype "passive"))
      (node (ref "U8") (pin "9") (pinfunction "AD0/SDO_9") (pintype "passive"))
    )
    (net (code "72") (name "Net-(U8-FSYNC)") (class "Default")
      (node (ref "R28") (pin "1") (pinfunction "1_1") (pintype "passive"))
      (node (ref "U8") (pin "11") (pinfunction "FSYNC_11") (pintype "passive"))
    )
    (net (code "73") (name "Net-(U8-REFOUT)") (class "Default")
      (node (ref "C17") (pin "1") (pinfunction "1_1") (pintype "passive"))
      (node (ref "U8") (pin "10") (pinfunction "REFOUT_10") (pintype "passive"))
    )
    (net (code "74") (name "VCC") (class "Default")
      (node (ref "C3") (pin "1") (pinfunction "1_1") (pintype "passive"))
      (node (ref "P1") (pin "1") (pinfunction "1_1") (pintype "passive"))
      (node (ref "Q1") (pin "3") (pinfunction "D_3") (pintype "passive"))
      (node (ref "R4") (pin "1") (pinfunction "1_1") (pintype "passive"))
      (node (ref "U10") (pin "13") (pinfunction "VM2_13") (pintype "passive"))
      (node (ref "U10") (pin "14") (pinfunction "VM3_14") (pintype "passive"))
      (node (ref "U10") (pin "24") (pinfunction "VM1_24") (pintype "passive"))
      (node (ref "U2") (pin "3") (pinfunction "IN_3") (pintype "passive"))
      (node (ref "U9") (pin "13") (pinfunction "VM2_13") (pintype "passive"))
      (node (ref "U9") (pin "14") (pinfunction "VM3_14") (pintype "passive"))
      (node (ref "U9") (pin "24") (pinfunction "VM1_24") (pintype "passive"))
    )
    (net (code "75") (name "unconnected-(J1-ID-Pad4)") (class "Default")
      (node (ref "J1") (pin "4") (pinfunction "ID_4") (pintype "passive+no_connect"))
    )
    (net (code "76") (name "unconnected-(J12-Pad2)") (class "Default")
      (node (ref "J12") (pin "2") (pinfunction "2_2") (pintype "passive"))
    )
    (net (code "77") (name "unconnected-(SW1-Pad3)") (class "Default")
      (node (ref "SW1") (pin "3") (pinfunction "3_3") (pintype "passive+no_connect"))
    )
    (net (code "78") (name "unconnected-(SW1-Pad4)") (class "Default")
      (node (ref "SW1") (pin "4") (pinfunction "4_4") (pintype "passive+no_connect"))
    )
    (net (code "79") (name "unconnected-(SW1-Pad5)") (class "Default")
      (node (ref "SW1") (pin "5") (pinfunction "5_5") (pintype "passive+no_connect"))
    )
    (net (code "80") (name "unconnected-(SW2-Pad1)") (class "Default")
      (node (ref "SW2") (pin "1") (pinfunction "1_1") (pintype "passive+no_connect"))
    )
    (net (code "81") (name "unconnected-(SW2-Pad3)") (class "Default")
      (node (ref "SW2") (pin "3") (pinfunction "3_3") (pintype "passive+no_connect"))
    )
    (net (code "82") (name "unconnected-(SW3-Pad1)") (class "Default")
      (node (ref "SW3") (pin "1") (pinfunction "1_1") (pintype "passive+no_connect"))
    )
    (net (code "83") (name "unconnected-(SW3-Pad3)") (class "Default")
      (node (ref "SW3") (pin "3") (pinfunction "3_3") (pintype "passive+no_connect"))
    )
    (net (code "84") (name "unconnected-(U4-INT#-Pad13)") (class "Default")
      (node (ref "U4") (pin "13") (pinfunction "INT#_13") (pintype "passive+no_connect"))
    )
    (net (code "85") (name "unconnected-(U5-NC-Pad17)") (class "Default")
      (node (ref "U5") (pin "17") (pinfunction "NC_17") (pintype "passive+no_connect"))
    )
    (net (code "86") (name "unconnected-(U5-NC-Pad18)") (class "Default")
      (node (ref "U5") (pin "18") (pinfunction "NC_18") (pintype "passive+no_connect"))
    )
    (net (code "87") (name "unconnected-(U5-NC-Pad19)") (class "Default")
      (node (ref "U5") (pin "19") (pinfunction "NC_19") (pintype "passive+no_connect"))
    )
    (net (code "88") (name "unconnected-(U5-NC-Pad20)") (class "Default")
      (node (ref "U5") (pin "20") (pinfunction "NC_20") (pintype "passive+no_connect"))
    )
    (net (code "89") (name "unconnected-(U5-NC-Pad21)") (class "Default")
      (node (ref "U5") (pin "21") (pinfunction "NC_21") (pintype "passive+no_connect"))
    )
    (net (code "90") (name "unconnected-(U5-NC-Pad22)") (class "Default")
      (node (ref "U5") (pin "22") (pinfunction "NC_22") (pintype "passive+no_connect"))
    )
    (net (code "91") (name "unconnected-(U5-NC-Pad32)") (class "Default")
      (node (ref "U5") (pin "32") (pinfunction "NC_32") (pintype "passive+no_connect"))
    )
    (net (code "92") (name "unconnected-(U7-CHR0-Pad15)") (class "Default")
      (node (ref "U7") (pin "15") (pinfunction "CHR0_15") (pintype "passive+no_connect"))
    )
    (net (code "93") (name "unconnected-(U7-CHR1-Pad14)") (class "Default")
      (node (ref "U7") (pin "14") (pinfunction "CHR1_14") (pintype "passive+no_connect"))
    )
    (net (code "94") (name "unconnected-(U7-CHREN-Pad13)") (class "Default")
      (node (ref "U7") (pin "13") (pinfunction "CHREN_13") (pintype "passive+no_connect"))
    )
    (net (code "95") (name "unconnected-(U7-CTS-Pad23)") (class "Default")
      (node (ref "U7") (pin "23") (pinfunction "CTS_23") (pintype "passive+no_connect"))
    )
    (net (code "96") (name "unconnected-(U7-DCD-Pad1)") (class "Default")
      (node (ref "U7") (pin "1") (pinfunction "DCD_1") (pintype "passive+no_connect"))
    )
    (net (code "97") (name "unconnected-(U7-DSR-Pad27)") (class "Default")
      (node (ref "U7") (pin "27") (pinfunction "DSR_27") (pintype "passive+no_connect"))
    )
    (net (code "98") (name "unconnected-(U7-GPIO.0{slash}TXT-Pad19)") (class "Default")
      (node (ref "U7") (pin "19") (pinfunction "GPIO.0/TXT_19") (pintype "passive+no_connect"))
    )
    (net (code "99") (name "unconnected-(U7-GPIO.1{slash}RXT-Pad18)") (class "Default")
      (node (ref "U7") (pin "18") (pinfunction "GPIO.1/RXT_18") (pintype "passive+no_connect"))
    )
    (net (code "100") (name "unconnected-(U7-GPIO.2{slash}RS485-Pad17)") (class "Default")
      (node (ref "U7") (pin "17") (pinfunction "GPIO.2/RS485_17") (pintype "passive+no_connect"))
    )
    (net (code "101") (name "unconnected-(U7-GPIO.3{slash}WAKEUP-Pad16)") (class "Default")
      (node (ref "U7") (pin "16") (pinfunction "GPIO.3/WAKEUP_16") (pintype "passive+no_connect"))
    )
    (net (code "102") (name "unconnected-(U7-GPIO.4-Pad22)") (class "Default")
      (node (ref "U7") (pin "22") (pinfunction "GPIO.4_22") (pintype "passive+no_connect"))
    )
    (net (code "103") (name "unconnected-(U7-GPIO.5-Pad21)") (class "Default")
      (node (ref "U7") (pin "21") (pinfunction "GPIO.5_21") (pintype "passive+no_connect"))
    )
    (net (code "104") (name "unconnected-(U7-GPIO.6-Pad20)") (class "Default")
      (node (ref "U7") (pin "20") (pinfunction "GPIO.6_20") (pintype "passive+no_connect"))
    )
    (net (code "105") (name "unconnected-(U7-NC-Pad10)") (class "Default")
      (node (ref "U7") (pin "10") (pinfunction "NC_10") (pintype "passive+no_connect"))
    )
    (net (code "106") (name "unconnected-(U7-RI{slash}CLK-Pad2)") (class "Default")
      (node (ref "U7") (pin "2") (pinfunction "RI/CLK_2") (pintype "passive+no_connect"))
    )
    (net (code "107") (name "unconnected-(U7-SUSPEND-Pad12)") (class "Default")
      (node (ref "U7") (pin "12") (pinfunction "SUSPEND_12") (pintype "passive+no_connect"))
    )
    (net (code "108") (name "unconnected-(U8-AUX_CL-Pad7)") (class "Default")
      (node (ref "U8") (pin "7") (pinfunction "AUX_CL_7") (pintype "passive+no_connect"))
    )
    (net (code "109") (name "unconnected-(U8-AUX_DA-Pad21)") (class "Default")
      (node (ref "U8") (pin "21") (pinfunction "AUX_DA_21") (pintype "passive+no_connect"))
    )
    (net (code "110") (name "unconnected-(U8-EXP-Pad25)") (class "Default")
      (node (ref "U8") (pin "25") (pinfunction "EXP_25") (pintype "passive+no_connect"))
    )
    (net (code "111") (name "unconnected-(U8-INT-Pad12)") (class "Default")
      (node (ref "U8") (pin "12") (pinfunction "INT_12") (pintype "passive+no_connect"))
    )
    (net (code "112") (name "unconnected-(U8-NC-Pad2)") (class "Default")
      (node (ref "U8") (pin "2") (pinfunction "NC_2") (pintype "passive+no_connect"))
    )
    (net (code "113") (name "unconnected-(U8-NC-Pad3)") (class "Default")
      (node (ref "U8") (pin "3") (pinfunction "NC_3") (pintype "passive+no_connect"))
    )
    (net (code "114") (name "unconnected-(U8-NC-Pad4)") (class "Default")
      (node (ref "U8") (pin "4") (pinfunction "NC_4") (pintype "passive+no_connect"))
    )
    (net (code "115") (name "unconnected-(U8-NC-Pad5)") (class "Default")
      (node (ref "U8") (pin "5") (pinfunction "NC_5") (pintype "passive+no_connect"))
    )
    (net (code "116") (name "unconnected-(U8-NC-Pad6)") (class "Default")
      (node (ref "U8") (pin "6") (pinfunction "NC_6") (pintype "passive+no_connect"))
    )
    (net (code "117") (name "unconnected-(U8-NC-Pad14)") (class "Default")
      (node (ref "U8") (pin "14") (pinfunction "NC_14") (pintype "passive+no_connect"))
    )
    (net (code "118") (name "unconnected-(U8-NC-Pad15)") (class "Default")
      (node (ref "U8") (pin "15") (pinfunction "NC_15") (pintype "passive+no_connect"))
    )
    (net (code "119") (name "unconnected-(U8-NC-Pad16)") (class "Default")
      (node (ref "U8") (pin "16") (pinfunction "NC_16") (pintype "passive+no_connect"))
    )
    (net (code "120") (name "unconnected-(U8-NC-Pad17)") (class "Default")
      (node (ref "U8") (pin "17") (pinfunction "NC_17") (pintype "passive+no_connect"))
    )
    (net (code "121") (name "unconnected-(U8-RESV-Pad19)") (class "Default")
      (node (ref "U8") (pin "19") (pinfunction "RESV_19") (pintype "passive+no_connect"))
    )
  )
)
